# US.net
KiCad netlist of a schematic drawn in EAGLE
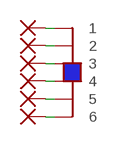
[diagram p0: schematic, sheet 1]

(export (version "E")
  (design (tool "Eeschema 10.0.6"))
  (components
    (comp (ref "C1")
      (value "6P6C_FEMALESMD")
      (footprint "eagle-import:6P6C_FEMALE")
      (libsource (lib "eagle-import") (part "6P6C_FEMALESMD"))
    )
    (comp (ref "PAD1")
      (value "2,54/1,0")
      (footprint "eagle-import:2,54_1,0")
      (libsource (lib "eagle-import") (part "2,54/1,0"))
    )
    (comp (ref "PAD2")
      (value "2,54/1,0")
      (footprint "eagle-import:2,54_1,0")
      (libsource (lib "eagle-import") (part "2,54/1,0"))
    )
    (comp (ref "PAD3")
      (value "2,54/1,0")
      (footprint "eagle-import:2,54_1,0")
      (libsource (lib "eagle-import") (part "2,54/1,0"))
    )
    (comp (ref "PAD4")
      (value "2,54/1,0")
      (footprint "eagle-import:2,54_1,0")
      (libsource (lib "eagle-import") (part "2,54/1,0"))
    )
    (comp (ref "PAD5")
      (value "2,54/1,0")
      (footprint "eagle-import:2,54_1,0")
      (libsource (lib "eagle-import") (part "2,54/1,0"))
    )
    (comp (ref "PAD6")
      (value "2,54/1,0")
      (footprint "eagle-import:2,54_1,0")
      (libsource (lib "eagle-import") (part "2,54/1,0"))
    )
  )
  (nets
    (net (code "1") (name "Net-(PAD1-P)") (class "Default")
      (node (ref "C1") (pin "1") (pinfunction "1_1") (pintype "bidirectional"))
      (node (ref "PAD1") (pin "1") (pinfunction "P_1") (pintype "passive"))
    )
    (net (code "2") (name "Net-(PAD2-P)") (class "Default")
      (node (ref "C1") (pin "2") (pinfunction "2_2") (pintype "bidirectional"))
      (node (ref "PAD2") (pin "1") (pinfunction "P_1") (pintype "passive"))
    )
    (net (code "3") (name "Net-(PAD3-P)") (class "Default")
      (node (ref "C1") (pin "3") (pinfunction "3_3") (pintype "bidirectional"))
      (node (ref "PAD3") (pin "1") (pinfunction "P_1") (pintype "passive"))
    )
    (net (code "4") (name "Net-(PAD4-P)") (class "Default")
      (node (ref "C1") (pin "4") (pinfunction "4_4") (pintype "bidirectional"))
      (node (ref "PAD4") (pin "1") (pinfunction "P_1") (pintype "passive"))
    )
    (net (code "5") (name "Net-(PAD5-P)") (class "Default")
      (node (ref "C1") (pin "5") (pinfunction "5_5") (pintype "bidirectional"))
      (node (ref "PAD5") (pin "1") (pinfunction "P_1") (pintype "passive"))
    )
    (net (code "6") (name "Net-(PAD6-P)") (class "Default")
      (node (ref "C1") (pin "6") (pinfunction "6_6") (pintype "bidirectional"))
      (node (ref "PAD6") (pin "1") (pinfunction "P_1") (pintype "passive"))
    )
  )
)
